# cm4.net
KiCad netlist of a schematic drawn in EAGLE
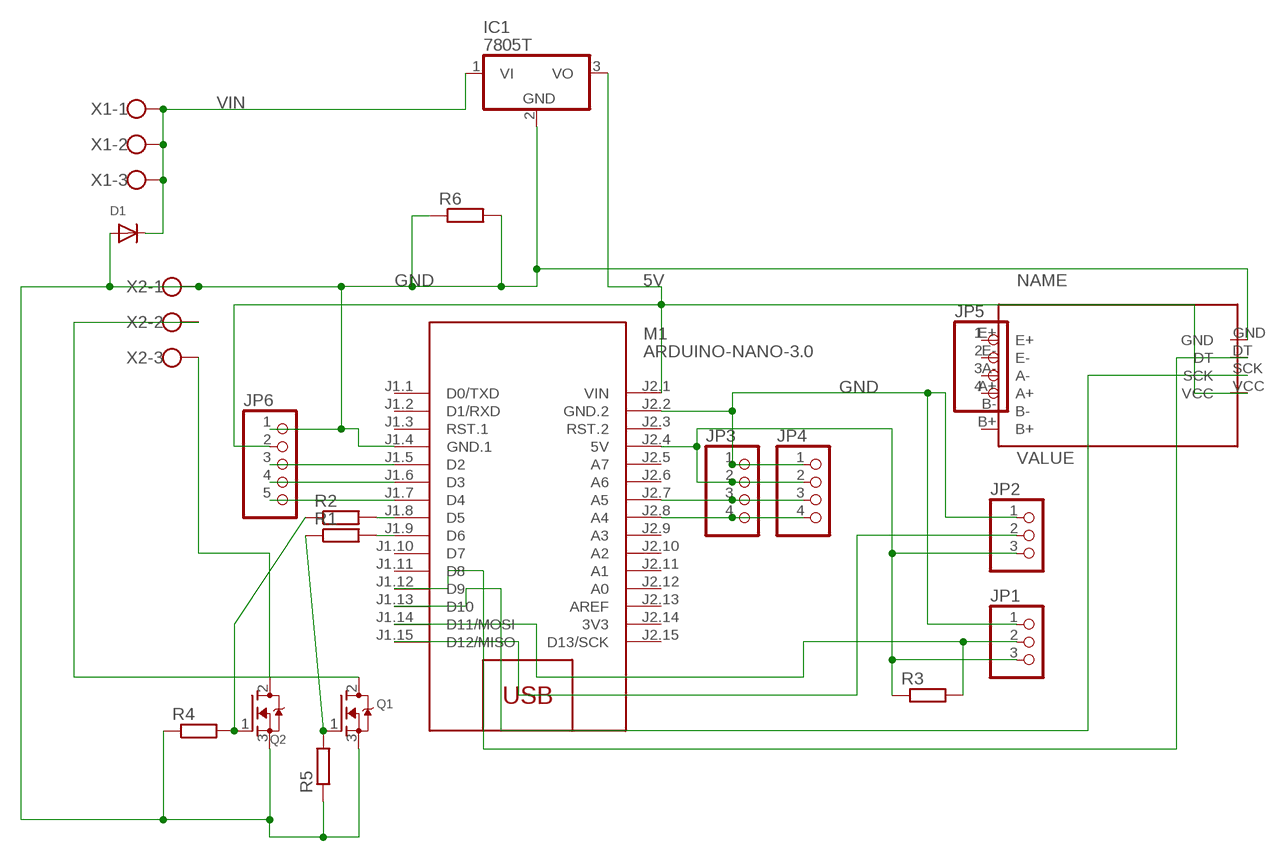
[diagram p0: schematic, sheet 1]

(export (version "E")
  (design (tool "Eeschema 10.0.6"))
  (components
    (comp (ref "D1")
      (value "DIODEDO-1N4148")
      (footprint "eagle-import:DO-1N4148")
      (libsource (lib "eagle-import") (part "DIODEDO-1N4148"))
    )
    (comp (ref "IC1")
      (value "7805T")
      (footprint "eagle-import:TO220H")
      (libsource (lib "eagle-import") (part "78T05"))
    )
    (comp (ref "JP1")
      (value "PINHD-1X3")
      (footprint "eagle-import:1X03")
      (libsource (lib "eagle-import") (part "PINHD-1X3"))
    )
    (comp (ref "JP2")
      (value "PINHD-1X3")
      (footprint "eagle-import:1X03")
      (libsource (lib "eagle-import") (part "PINHD-1X3"))
    )
    (comp (ref "JP3")
      (value "PINHD-1X4")
      (footprint "eagle-import:1X04")
      (libsource (lib "eagle-import") (part "PINHD-1X4"))
    )
    (comp (ref "JP4")
      (value "PINHD-1X4")
      (footprint "eagle-import:1X04")
      (libsource (lib "eagle-import") (part "PINHD-1X4"))
    )
    (comp (ref "JP5")
      (value "PINHD-1X4")
      (footprint "eagle-import:1X04")
      (libsource (lib "eagle-import") (part "PINHD-1X4"))
    )
    (comp (ref "JP6")
      (value "PINHD-1X5")
      (footprint "eagle-import:1X05")
      (libsource (lib "eagle-import") (part "PINHD-1X5"))
    )
    (comp (ref "M1")
      (value "ARDUINO-NANO-3.0")
      (footprint "eagle-import:ARDUINO-NANO-3.0")
      (libsource (lib "eagle-import") (part "ARDUINO-NANO-3.0"))
    )
    (comp (ref "Q1")
      (value "MOSFET-NGDS_TO220V")
      (footprint "eagle-import:TO220V")
      (libsource (lib "eagle-import") (part "MOSFET-NGDS_TO220V"))
    )
    (comp (ref "Q2")
      (value "MOSFET-NGDS_TO220V")
      (footprint "eagle-import:TO220V")
      (libsource (lib "eagle-import") (part "MOSFET-NGDS_TO220V"))
    )
    (comp (ref "R1")
      (value "R-EU_0207/7")
      (footprint "eagle-import:0207_7")
      (libsource (lib "eagle-import") (part "R-EU_0207/7"))
    )
    (comp (ref "R2")
      (value "R-EU_0207/7")
      (footprint "eagle-import:0207_7")
      (libsource (lib "eagle-import") (part "R-EU_0207/7"))
    )
    (comp (ref "R3")
      (value "R-EU_0207/7")
      (footprint "eagle-import:0207_7")
      (libsource (lib "eagle-import") (part "R-EU_0207/7"))
    )
    (comp (ref "R4")
      (value "R-EU_0207/7")
      (footprint "eagle-import:0207_7")
      (libsource (lib "eagle-import") (part "R-EU_0207/7"))
    )
    (comp (ref "R5")
      (value "R-EU_0207/7")
      (footprint "eagle-import:0207_7")
      (libsource (lib "eagle-import") (part "R-EU_0207/7"))
    )
    (comp (ref "R6")
      (value "R-EU_0207/7")
      (footprint "eagle-import:0207_7")
      (libsource (lib "eagle-import") (part "R-EU_0207/7"))
    )
    (comp (ref "U$1")
      (value "HX711A")
      (footprint "eagle-import:HX711")
      (libsource (lib "eagle-import") (part "HX711A"))
    )
    (comp (ref "X1")
      (value "W237-103")
      (footprint "eagle-import:W237-103")
      (fields (field (name "MPN") "237-103"))
      (libsource (lib "eagle-import") (part "W237-103"))
    )
    (comp (ref "X2")
      (value "W237-103")
      (footprint "eagle-import:W237-103")
      (fields (field (name "MPN") "237-103"))
      (libsource (lib "eagle-import") (part "W237-103"))
    )
  )
  (nets
    (net (code "1") (name "/3V3") (class "Default")
      (node (ref "M1") (pin "J2.14") (pinfunction "3V3_J2.14") (pintype "power_in"))
    )
    (net (code "2") (name "/5V") (class "Default")
      (node (ref "IC1") (pin "3") (pinfunction "VO_3") (pintype "passive"))
      (node (ref "JP6") (pin "2") (pinfunction "2_2") (pintype "passive"))
      (node (ref "M1") (pin "J2.1") (pinfunction "VIN_J2.1") (pintype "power_in"))
      (node (ref "U$1") (pin "VCC") (pinfunction "VCC_VCC") (pintype "bidirectional"))
    )
    (net (code "3") (name "/GND") (class "Default")
      (node (ref "D1") (pin "A") (pinfunction "A_A") (pintype "passive"))
      (node (ref "IC1") (pin "2") (pinfunction "GND_2") (pintype "passive"))
      (node (ref "JP1") (pin "1") (pinfunction "1_1") (pintype "passive"))
      (node (ref "JP2") (pin "1") (pinfunction "1_1") (pintype "passive"))
      (node (ref "JP3") (pin "1") (pinfunction "1_1") (pintype "passive"))
      (node (ref "JP4") (pin "1") (pinfunction "1_1") (pintype "passive"))
      (node (ref "JP6") (pin "1") (pinfunction "1_1") (pintype "passive"))
      (node (ref "M1") (pin "J1.4") (pinfunction "GND.1_J1.4") (pintype "power_in"))
      (node (ref "M1") (pin "J2.2") (pinfunction "GND.2_J2.2") (pintype "power_in"))
      (node (ref "Q1") (pin "3") (pinfunction "S_3") (pintype "bidirectional"))
      (node (ref "Q2") (pin "3") (pinfunction "S_3") (pintype "bidirectional"))
      (node (ref "R4") (pin "1") (pinfunction "1_1") (pintype "passive"))
      (node (ref "R5") (pin "1") (pinfunction "1_1") (pintype "passive"))
      (node (ref "R6") (pin "1") (pinfunction "1_1") (pintype "passive"))
      (node (ref "R6") (pin "2") (pinfunction "2_2") (pintype "passive"))
      (node (ref "U$1") (pin "GND") (pinfunction "GND_GND") (pintype "bidirectional"))
      (node (ref "X2") (pin "1") (pinfunction "KL_1") (pintype "passive"))
    )
    (net (code "4") (name "/VIN") (class "Default")
      (node (ref "D1") (pin "C") (pinfunction "C_C") (pintype "passive"))
      (node (ref "IC1") (pin "1") (pinfunction "VI_1") (pintype "input"))
      (node (ref "X1") (pin "1") (pinfunction "KL_1") (pintype "passive"))
      (node (ref "X1") (pin "2") (pinfunction "KL_2") (pintype "passive"))
      (node (ref "X1") (pin "3") (pinfunction "KL_3") (pintype "passive"))
    )
    (net (code "5") (name "Net-(JP5-Pad1)") (class "Default")
      (node (ref "JP5") (pin "1") (pinfunction "1_1") (pintype "passive"))
      (node (ref "U$1") (pin "E+") (pinfunction "E+_E+") (pintype "bidirectional"))
    )
    (net (code "6") (name "Net-(JP5-Pad2)") (class "Default")
      (node (ref "JP5") (pin "2") (pinfunction "2_2") (pintype "passive"))
      (node (ref "U$1") (pin "E-") (pinfunction "E-_E-") (pintype "bidirectional"))
    )
    (net (code "7") (name "Net-(JP5-Pad3)") (class "Default")
      (node (ref "JP5") (pin "3") (pinfunction "3_3") (pintype "passive"))
      (node (ref "U$1") (pin "A-") (pinfunction "A-_A-") (pintype "bidirectional"))
    )
    (net (code "8") (name "Net-(JP5-Pad4)") (class "Default")
      (node (ref "JP5") (pin "4") (pinfunction "4_4") (pintype "passive"))
      (node (ref "U$1") (pin "A+") (pinfunction "A+_A+") (pintype "bidirectional"))
    )
    (net (code "9") (name "Net-(M1-5V)") (class "Default")
      (node (ref "JP1") (pin "3") (pinfunction "3_3") (pintype "passive"))
      (node (ref "JP2") (pin "3") (pinfunction "3_3") (pintype "passive"))
      (node (ref "JP3") (pin "2") (pinfunction "2_2") (pintype "passive"))
      (node (ref "JP4") (pin "2") (pinfunction "2_2") (pintype "passive"))
      (node (ref "M1") (pin "J2.4") (pinfunction "5V_J2.4") (pintype "power_in"))
      (node (ref "R3") (pin "1") (pinfunction "1_1") (pintype "passive"))
    )
    (net (code "10") (name "Net-(M1-A4)") (class "Default")
      (node (ref "JP3") (pin "4") (pinfunction "4_4") (pintype "passive"))
      (node (ref "JP4") (pin "4") (pinfunction "4_4") (pintype "passive"))
      (node (ref "M1") (pin "J2.8") (pinfunction "A4_J2.8") (pintype "bidirectional"))
    )
    (net (code "11") (name "Net-(M1-A5)") (class "Default")
      (node (ref "JP3") (pin "3") (pinfunction "3_3") (pintype "passive"))
      (node (ref "JP4") (pin "3") (pinfunction "3_3") (pintype "passive"))
      (node (ref "M1") (pin "J2.7") (pinfunction "A5_J2.7") (pintype "bidirectional"))
    )
    (net (code "12") (name "Net-(M1-D2)") (class "Default")
      (node (ref "JP6") (pin "3") (pinfunction "3_3") (pintype "passive"))
      (node (ref "M1") (pin "J1.5") (pinfunction "D2_J1.5") (pintype "bidirectional"))
    )
    (net (code "13") (name "Net-(M1-D3)") (class "Default")
      (node (ref "JP6") (pin "4") (pinfunction "4_4") (pintype "passive"))
      (node (ref "M1") (pin "J1.6") (pinfunction "D3_J1.6") (pintype "bidirectional"))
    )
    (net (code "14") (name "Net-(M1-D4)") (class "Default")
      (node (ref "JP6") (pin "5") (pinfunction "5_5") (pintype "passive"))
      (node (ref "M1") (pin "J1.7") (pinfunction "D4_J1.7") (pintype "bidirectional"))
    )
    (net (code "15") (name "Net-(M1-D5)") (class "Default")
      (node (ref "M1") (pin "J1.8") (pinfunction "D5_J1.8") (pintype "bidirectional"))
      (node (ref "R2") (pin "2") (pinfunction "2_2") (pintype "passive"))
    )
    (net (code "16") (name "Net-(M1-D6)") (class "Default")
      (node (ref "M1") (pin "J1.9") (pinfunction "D6_J1.9") (pintype "bidirectional"))
      (node (ref "R1") (pin "2") (pinfunction "2_2") (pintype "passive"))
    )
    (net (code "17") (name "Net-(M1-D9)") (class "Default")
      (node (ref "M1") (pin "J1.12") (pinfunction "D9_J1.12") (pintype "bidirectional"))
      (node (ref "U$1") (pin "DT") (pinfunction "DT_DT") (pintype "bidirectional"))
    )
    (net (code "18") (name "Net-(M1-D10)") (class "Default")
      (node (ref "M1") (pin "J1.13") (pinfunction "D10_J1.13") (pintype "bidirectional"))
      (node (ref "U$1") (pin "SCK") (pinfunction "SCK_SCK") (pintype "bidirectional"))
    )
    (net (code "19") (name "Net-(M1-D11{slash}MOSI)") (class "Default")
      (node (ref "JP1") (pin "2") (pinfunction "2_2") (pintype "passive"))
      (node (ref "M1") (pin "J1.14") (pinfunction "D11/MOSI_J1.14") (pintype "bidirectional"))
      (node (ref "R3") (pin "2") (pinfunction "2_2") (pintype "passive"))
    )
    (net (code "20") (name "Net-(M1-D12{slash}MISO)") (class "Default")
      (node (ref "JP2") (pin "2") (pinfunction "2_2") (pintype "passive"))
      (node (ref "M1") (pin "J1.15") (pinfunction "D12/MISO_J1.15") (pintype "bidirectional"))
    )
    (net (code "21") (name "Net-(Q1-D)") (class "Default")
      (node (ref "Q1") (pin "2") (pinfunction "D_2") (pintype "bidirectional"))
      (node (ref "X2") (pin "2") (pinfunction "KL_2") (pintype "passive"))
    )
    (net (code "22") (name "Net-(Q1-G)") (class "Default")
      (node (ref "Q1") (pin "1") (pinfunction "G_1") (pintype "bidirectional"))
      (node (ref "R1") (pin "1") (pinfunction "1_1") (pintype "passive"))
      (node (ref "R5") (pin "2") (pinfunction "2_2") (pintype "passive"))
    )
    (net (code "23") (name "Net-(Q2-D)") (class "Default")
      (node (ref "Q2") (pin "2") (pinfunction "D_2") (pintype "bidirectional"))
      (node (ref "X2") (pin "3") (pinfunction "KL_3") (pintype "passive"))
    )
    (net (code "24") (name "Net-(Q2-G)") (class "Default")
      (node (ref "Q2") (pin "1") (pinfunction "G_1") (pintype "bidirectional"))
      (node (ref "R2") (pin "1") (pinfunction "1_1") (pintype "passive"))
      (node (ref "R4") (pin "2") (pinfunction "2_2") (pintype "passive"))
    )
    (net (code "25") (name "unconnected-(M1-A0-PadJ2.12)") (class "Default")
      (node (ref "M1") (pin "J2.12") (pinfunction "A0_J2.12") (pintype "bidirectional"))
    )
    (net (code "26") (name "unconnected-(M1-A1-PadJ2.11)") (class "Default")
      (node (ref "M1") (pin "J2.11") (pinfunction "A1_J2.11") (pintype "bidirectional"))
    )
    (net (code "27") (name "unconnected-(M1-A2-PadJ2.10)") (class "Default")
      (node (ref "M1") (pin "J2.10") (pinfunction "A2_J2.10") (pintype "bidirectional"))
    )
    (net (code "28") (name "unconnected-(M1-A3-PadJ2.9)") (class "Default")
      (node (ref "M1") (pin "J2.9") (pinfunction "A3_J2.9") (pintype "bidirectional"))
    )
    (net (code "29") (name "unconnected-(M1-A6-PadJ2.6)") (class "Default")
      (node (ref "M1") (pin "J2.6") (pinfunction "A6_J2.6") (pintype "bidirectional"))
    )
    (net (code "30") (name "unconnected-(M1-A7-PadJ2.5)") (class "Default")
      (node (ref "M1") (pin "J2.5") (pinfunction "A7_J2.5") (pintype "bidirectional"))
    )
    (net (code "31") (name "unconnected-(M1-AREF-PadJ2.13)") (class "Default")
      (node (ref "M1") (pin "J2.13") (pinfunction "AREF_J2.13") (pintype "bidirectional"))
    )
    (net (code "32") (name "unconnected-(M1-D0{slash}TXD-PadJ1.1)") (class "Default")
      (node (ref "M1") (pin "J1.1") (pinfunction "D0/TXD_J1.1") (pintype "bidirectional"))
    )
    (net (code "33") (name "unconnected-(M1-D1{slash}RXD-PadJ1.2)") (class "Default")
      (node (ref "M1") (pin "J1.2") (pinfunction "D1/RXD_J1.2") (pintype "bidirectional"))
    )
    (net (code "34") (name "unconnected-(M1-D7-PadJ1.10)") (class "Default")
      (node (ref "M1") (pin "J1.10") (pinfunction "D7_J1.10") (pintype "bidirectional"))
    )
    (net (code "35") (name "unconnected-(M1-D8-PadJ1.11)") (class "Default")
      (node (ref "M1") (pin "J1.11") (pinfunction "D8_J1.11") (pintype "bidirectional"))
    )
    (net (code "36") (name "unconnected-(M1-D13{slash}SCK-PadJ2.15)") (class "Default")
      (node (ref "M1") (pin "J2.15") (pinfunction "D13/SCK_J2.15") (pintype "bidirectional"))
    )
    (net (code "37") (name "unconnected-(M1-RST.1-PadJ1.3)") (class "Default")
      (node (ref "M1") (pin "J1.3") (pinfunction "RST.1_J1.3") (pintype "bidirectional"))
    )
    (net (code "38") (name "unconnected-(M1-RST.2-PadJ2.3)") (class "Default")
      (node (ref "M1") (pin "J2.3") (pinfunction "RST.2_J2.3") (pintype "bidirectional"))
    )
    (net (code "39") (name "unconnected-(U$1-PadB+)") (class "Default")
      (node (ref "U$1") (pin "B+") (pinfunction "B+_B+") (pintype "bidirectional"))
    )
    (net (code "40") (name "unconnected-(U$1-PadB-)") (class "Default")
      (node (ref "U$1") (pin "B-") (pinfunction "B-_B-") (pintype "bidirectional"))
    )
  )
)
